# 11_Fun.net
KiCad netlist of a schematic drawn in Altium Designer
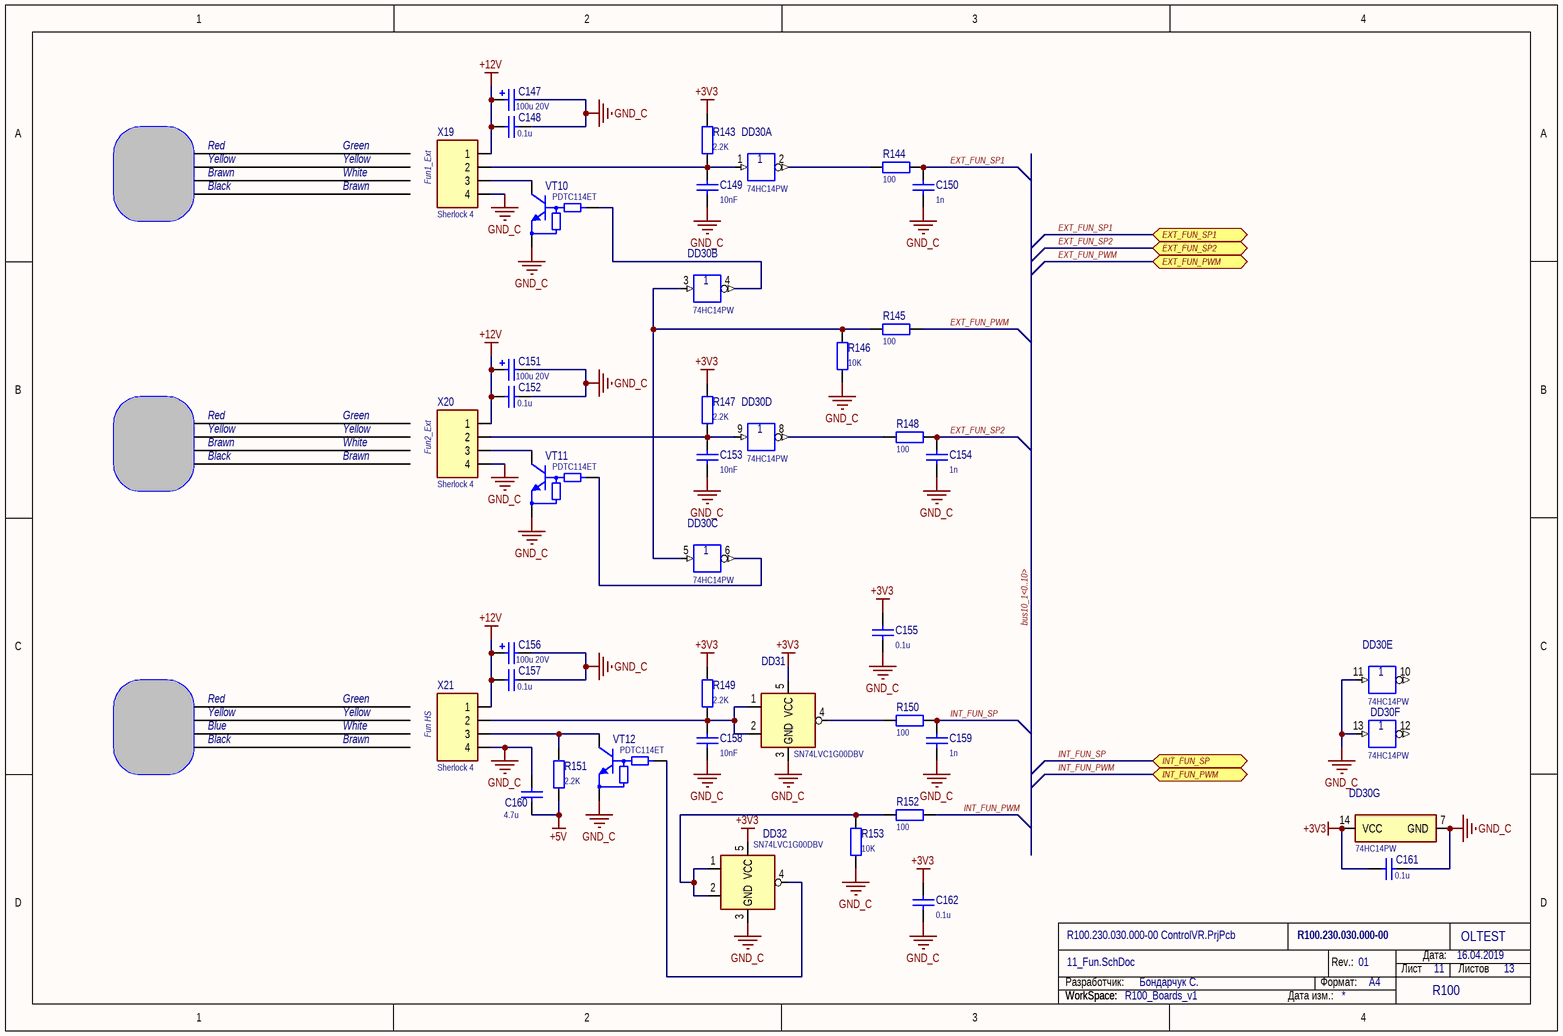
[diagram p0: 11_Fun.SchDoc]

(export (version "E")
  (design (tool "Eeschema 10.0.6"))
  (components
    (comp (ref "C147")
      (value "100u 20V")
      (footprint "mainLib:TAJD")
      (description "SMD SIZE D TANTALUM AVX 20V 10%")
      (fields (field (name "PARTNUMBER") "TAJD107K020RNJ") (field (name "MANUFACTURER") "AVX"))
      (libsource (lib "mainRCLib") (part "TECAP 100u 20V 10%"))
    )
    (comp (ref "C148")
      (value "0.1u")
      (footprint "mainLib:SMD_C_0603")
      (description "SMD C 0603 MURATA 50V 10% X7R")
      (fields (field (name "PARTNUMBER") "GRM188R71H104K") (field (name "MANUFACTURER") "MURATA"))
      (libsource (lib "mainRCLib") (part "C0603 0.1u 50V 10%"))
    )
    (comp (ref "C149")
      (value "10nF")
      (footprint "mainLib:SMD_C_0603")
      (description "SMD C 0603 MURATA 100V 10% X7R")
      (fields (field (name "PARTNUMBER") "GRJ188R72A103KE11#") (field (name "MANUFACTURER") "MURATA"))
      (libsource (lib "mainRCLib") (part "C0603 10nF 100V 10%"))
    )
    (comp (ref "C150")
      (value "1n")
      (footprint "mainLib:SMD_C_0603")
      (description "SMD C 0603 MURATA 50V 5% NP0")
      (fields (field (name "PARTNUMBER") "GRM1885C1H102JA01") (field (name "MANUFACTURER") "MURATA"))
      (libsource (lib "mainRCLib") (part "C0603 1n 50V 5%"))
    )
    (comp (ref "C151")
      (value "100u 20V")
      (footprint "mainLib:TAJD")
      (description "SMD SIZE D TANTALUM AVX 20V 10%")
      (fields (field (name "PARTNUMBER") "TAJD107K020RNJ") (field (name "MANUFACTURER") "AVX"))
      (libsource (lib "mainRCLib") (part "TECAP 100u 20V 10%"))
    )
    (comp (ref "C152")
      (value "0.1u")
      (footprint "mainLib:SMD_C_0603")
      (description "SMD C 0603 MURATA 50V 10% X7R")
      (fields (field (name "PARTNUMBER") "GRM188R71H104K") (field (name "MANUFACTURER") "MURATA"))
      (libsource (lib "mainRCLib") (part "C0603 0.1u 50V 10%"))
    )
    (comp (ref "C153")
      (value "10nF")
      (footprint "mainLib:SMD_C_0603")
      (description "SMD C 0603 MURATA 100V 10% X7R")
      (fields (field (name "PARTNUMBER") "GRJ188R72A103KE11#") (field (name "MANUFACTURER") "MURATA"))
      (libsource (lib "mainRCLib") (part "C0603 10nF 100V 10%"))
    )
    (comp (ref "C154")
      (value "1n")
      (footprint "mainLib:SMD_C_0603")
      (description "SMD C 0603 MURATA 50V 5% NP0")
      (fields (field (name "PARTNUMBER") "GRM1885C1H102JA01") (field (name "MANUFACTURER") "MURATA"))
      (libsource (lib "mainRCLib") (part "C0603 1n 50V 5%"))
    )
    (comp (ref "C155")
      (value "0.1u")
      (footprint "mainLib:SMD_C_0603")
      (description "SMD C 0603 MURATA 50V 10% X7R")
      (fields (field (name "PARTNUMBER") "GRM188R71H104K") (field (name "MANUFACTURER") "MURATA"))
      (libsource (lib "mainRCLib") (part "C0603 0.1u 50V 10%"))
    )
    (comp (ref "C156")
      (value "100u 20V")
      (footprint "mainLib:TAJD")
      (description "SMD SIZE D TANTALUM AVX 20V 10%")
      (fields (field (name "PARTNUMBER") "TAJD107K020RNJ") (field (name "MANUFACTURER") "AVX"))
      (libsource (lib "mainRCLib") (part "TECAP 100u 20V 10%"))
    )
    (comp (ref "C157")
      (value "0.1u")
      (footprint "mainLib:SMD_C_0603")
      (description "SMD C 0603 MURATA 50V 10% X7R")
      (fields (field (name "PARTNUMBER") "GRM188R71H104K") (field (name "MANUFACTURER") "MURATA"))
      (libsource (lib "mainRCLib") (part "C0603 0.1u 50V 10%"))
    )
    (comp (ref "C158")
      (value "10nF")
      (footprint "mainLib:SMD_C_0603")
      (description "SMD C 0603 MURATA 100V 10% X7R")
      (fields (field (name "PARTNUMBER") "GRJ188R72A103KE11#") (field (name "MANUFACTURER") "MURATA"))
      (libsource (lib "mainRCLib") (part "C0603 10nF 100V 10%"))
    )
    (comp (ref "C159")
      (value "1n")
      (footprint "mainLib:SMD_C_0603")
      (description "SMD C 0603 MURATA 50V 5% NP0")
      (fields (field (name "PARTNUMBER") "GRM1885C1H102JA01") (field (name "MANUFACTURER") "MURATA"))
      (libsource (lib "mainRCLib") (part "C0603 1n 50V 5%"))
    )
    (comp (ref "C160")
      (value "4.7u")
      (footprint "mainLib:SMD_C_0805")
      (description "SMD C 0805 MURATA 50V 5% NP0")
      (fields (field (name "PARTNUMBER") "GRM21BR61E475M") (field (name "MANUFACTURER") "MURATA"))
      (libsource (lib "mainRCLib") (part "C0805 4.7u 25V 20%  X5R"))
    )
    (comp (ref "C161")
      (value "0.1u")
      (footprint "mainLib:SMD_C_0603")
      (description "SMD C 0603 MURATA 50V 10% X7R")
      (fields (field (name "PARTNUMBER") "GRM188R71H104K") (field (name "MANUFACTURER") "MURATA"))
      (libsource (lib "mainRCLib") (part "C0603 0.1u 50V 10%"))
    )
    (comp (ref "C162")
      (value "0.1u")
      (footprint "mainLib:SMD_C_0603")
      (description "SMD C 0603 MURATA 50V 10% X7R")
      (fields (field (name "PARTNUMBER") "GRM188R71H104K") (field (name "MANUFACTURER") "MURATA"))
      (libsource (lib "mainRCLib") (part "C0603 0.1u 50V 10%"))
    )
    (comp (ref "DD30")
      (value "74HC14PW")
      (footprint "mainLib:TSSOP14")
      (description "Quadruple 2-Input Positive-OR Gates, PW0014A")
      (fields (field (name "MANUFACTURER") "Texas Instruments"))
      (libsource (lib "mainLib") (part "74HC14"))
    )
    (comp (ref "DD31")
      (value "SN74LVC1G00DBV")
      (footprint "mainLib:SOT-23(DBV)")
      (description "2-in NAND")
      (fields (field (name "MANUFACTURER") "Texas Instruments"))
      (libsource (lib "mainLib") (part "SN74LVC1G00DBV"))
    )
    (comp (ref "DD32")
      (value "SN74LVC1G00DBV")
      (footprint "mainLib:SOT-23(DBV)")
      (description "2-in NAND")
      (fields (field (name "MANUFACTURER") "Texas Instruments"))
      (libsource (lib "mainLib") (part "SN74LVC1G00DBV"))
    )
    (comp (ref "R143")
      (value "2.2K")
      (footprint "mainLib:SMD_R_0603")
      (description "SMD R 0603 VISHAY 0.1W 75V 1% 100ppm")
      (fields (field (name "PARTNUMBER") "CRCW06032K20FK") (field (name "MANUFACTURER") "VISHAY"))
      (libsource (lib "mainRCLib") (part "R0603 2.2K 1%"))
    )
    (comp (ref "R144")
      (value "100")
      (footprint "SMD_R_0603")
      (description "SMD R 0603 VISHAY 0.1W 75V 1% 100ppm")
      (fields (field (name "PARTNUMBER") "CRCW0603100RFK") (field (name "MANUFACTURER") "VISHAY"))
      (libsource (lib "mainRCLib") (part "R0603 100 1%"))
    )
    (comp (ref "R145")
      (value "100")
      (footprint "SMD_R_0603")
      (description "SMD R 0603 VISHAY 0.1W 75V 1% 100ppm")
      (fields (field (name "PARTNUMBER") "CRCW0603100RFK") (field (name "MANUFACTURER") "VISHAY"))
      (libsource (lib "mainRCLib") (part "R0603 100 1%"))
    )
    (comp (ref "R146")
      (value "10K")
      (footprint "SMD_R_0603")
      (description "SMD R 0603 VISHAY 0.1W 75V 1% 100ppm")
      (fields (field (name "PARTNUMBER") "CRCW060310K0FK") (field (name "MANUFACTURER") "VISHAY"))
      (libsource (lib "mainRCLib") (part "R0603 10К 1%"))
    )
    (comp (ref "R147")
      (value "2.2K")
      (footprint "mainLib:SMD_R_0603")
      (description "SMD R 0603 VISHAY 0.1W 75V 1% 100ppm")
      (fields (field (name "PARTNUMBER") "CRCW06032K20FK") (field (name "MANUFACTURER") "VISHAY"))
      (libsource (lib "mainRCLib") (part "R0603 2.2K 1%"))
    )
    (comp (ref "R148")
      (value "100")
      (footprint "SMD_R_0603")
      (description "SMD R 0603 VISHAY 0.1W 75V 1% 100ppm")
      (fields (field (name "PARTNUMBER") "CRCW0603100RFK") (field (name "MANUFACTURER") "VISHAY"))
      (libsource (lib "mainRCLib") (part "R0603 100 1%"))
    )
    (comp (ref "R149")
      (value "2.2K")
      (footprint "mainLib:SMD_R_0603")
      (description "SMD R 0603 VISHAY 0.1W 75V 1% 100ppm")
      (fields (field (name "PARTNUMBER") "CRCW06032K20FK") (field (name "MANUFACTURER") "VISHAY"))
      (libsource (lib "mainRCLib") (part "R0603 2.2K 1%"))
    )
    (comp (ref "R150")
      (value "100")
      (footprint "SMD_R_0603")
      (description "SMD R 0603 VISHAY 0.1W 75V 1% 100ppm")
      (fields (field (name "PARTNUMBER") "CRCW0603100RFK") (field (name "MANUFACTURER") "VISHAY"))
      (libsource (lib "mainRCLib") (part "R0603 100 1%"))
    )
    (comp (ref "R151")
      (value "2.2K")
      (footprint "mainLib:SMD_R_0603")
      (description "SMD R 0603 VISHAY 0.1W 75V 1% 100ppm")
      (fields (field (name "PARTNUMBER") "CRCW06032K20FK") (field (name "MANUFACTURER") "VISHAY"))
      (libsource (lib "mainRCLib") (part "R0603 2.2K 1%"))
    )
    (comp (ref "R152")
      (value "100")
      (footprint "SMD_R_0603")
      (description "SMD R 0603 VISHAY 0.1W 75V 1% 100ppm")
      (fields (field (name "PARTNUMBER") "CRCW0603100RFK") (field (name "MANUFACTURER") "VISHAY"))
      (libsource (lib "mainRCLib") (part "R0603 100 1%"))
    )
    (comp (ref "R153")
      (value "10K")
      (footprint "SMD_R_0603")
      (description "SMD R 0603 VISHAY 0.1W 75V 1% 100ppm")
      (fields (field (name "PARTNUMBER") "CRCW060310K0FK") (field (name "MANUFACTURER") "VISHAY"))
      (libsource (lib "mainRCLib") (part "R0603 10К 1%"))
    )
    (comp (ref "VT10")
      (value "PDTC114ET")
      (footprint "mainLib:SOT23-3")
      (description "Digital Transistor (BRT), R1=10 kOhm, R2=10 kOhm, NPN Transistor")
      (fields (field (name "MANUFACTURER") "On Semiconductor"))
      (libsource (lib "mainLib") (part "PDTC114ET"))
    )
    (comp (ref "VT11")
      (value "PDTC114ET")
      (footprint "mainLib:SOT23-3")
      (description "Digital Transistor (BRT), R1=10 kOhm, R2=10 kOhm, NPN Transistor")
      (fields (field (name "MANUFACTURER") "On Semiconductor"))
      (libsource (lib "mainLib") (part "PDTC114ET"))
    )
    (comp (ref "VT12")
      (value "PDTC114ET")
      (footprint "mainLib:SOT23-3")
      (description "Digital Transistor (BRT), R1=10 kOhm, R2=10 kOhm, NPN Transistor")
      (fields (field (name "MANUFACTURER") "On Semiconductor"))
      (libsource (lib "mainLib") (part "PDTC114ET"))
    )
    (comp (ref "X19")
      (value "Sherlock 4")
      (footprint "35362-0450")
      (description "Sherlock 4 Top, 2A 125V 2mm")
      (fields (field (name "PARTNUMBER") "35362-0450") (field (name "MANUFACTURER") "MOLEX"))
      (libsource (lib "mainLib") (part "35362-0450"))
    )
    (comp (ref "X20")
      (value "Sherlock 4")
      (footprint "35362-0450")
      (description "Sherlock 4 Top, 2A 125V 2mm")
      (fields (field (name "PARTNUMBER") "35362-0450") (field (name "MANUFACTURER") "MOLEX"))
      (libsource (lib "mainLib") (part "35362-0450"))
    )
    (comp (ref "X21")
      (value "Sherlock 4")
      (footprint "35362-0450")
      (description "Sherlock 4 Top, 2A 125V 2mm")
      (fields (field (name "PARTNUMBER") "35362-0450") (field (name "MANUFACTURER") "MOLEX"))
      (libsource (lib "mainLib") (part "35362-0450"))
    )
  )
  (nets
    (net (code "2") (name "+3V3") (class "Default")
      (node (ref "C155") (pin "2") (pinfunction "2_2") (pintype "passive"))
      (node (ref "C161") (pin "1") (pinfunction "1_1") (pintype "passive"))
      (node (ref "C162") (pin "2") (pinfunction "2_2") (pintype "passive"))
      (node (ref "DD30") (pin "14") (pinfunction "VCC_14") (pintype "power_in"))
      (node (ref "DD31") (pin "5") (pinfunction "VCC_5") (pintype "passive"))
      (node (ref "DD32") (pin "5") (pinfunction "VCC_5") (pintype "passive"))
      (node (ref "R143") (pin "2") (pinfunction "2_2") (pintype "passive"))
      (node (ref "R147") (pin "2") (pinfunction "2_2") (pintype "passive"))
      (node (ref "R149") (pin "2") (pinfunction "2_2") (pintype "passive"))
    )
    (net (code "3") (name "+5V") (class "Default")
      (node (ref "C160") (pin "1") (pinfunction "1_1") (pintype "passive"))
      (node (ref "R151") (pin "1") (pinfunction "1_1") (pintype "passive"))
    )
    (net (code "4") (name "+12V") (class "Default")
      (node (ref "C147") (pin "1") (pinfunction "1_1") (pintype "passive"))
      (node (ref "C148") (pin "1") (pinfunction "1_1") (pintype "passive"))
      (node (ref "C151") (pin "1") (pinfunction "1_1") (pintype "passive"))
      (node (ref "C152") (pin "1") (pinfunction "1_1") (pintype "passive"))
      (node (ref "C156") (pin "1") (pinfunction "1_1") (pintype "passive"))
      (node (ref "C157") (pin "1") (pinfunction "1_1") (pintype "passive"))
      (node (ref "X19") (pin "1") (pinfunction "1_1") (pintype "passive"))
      (node (ref "X20") (pin "1") (pinfunction "1_1") (pintype "passive"))
      (node (ref "X21") (pin "1") (pinfunction "1_1") (pintype "passive"))
    )
    (net (code "5") (name "/EXT_FUN_PWM") (class "Default")
      (node (ref "R145") (pin "2") (pinfunction "2_2") (pintype "passive"))
    )
    (net (code "6") (name "/EXT_FUN_SP1") (class "Default")
      (node (ref "C150") (pin "2") (pinfunction "2_2") (pintype "passive"))
      (node (ref "R144") (pin "2") (pinfunction "2_2") (pintype "passive"))
    )
    (net (code "7") (name "/EXT_FUN_SP2") (class "Default")
      (node (ref "C154") (pin "2") (pinfunction "2_2") (pintype "passive"))
      (node (ref "R148") (pin "2") (pinfunction "2_2") (pintype "passive"))
    )
    (net (code "8") (name "/INT_FUN_PWM") (class "Default")
      (node (ref "R152") (pin "2") (pinfunction "2_2") (pintype "passive"))
    )
    (net (code "9") (name "/INT_FUN_SP") (class "Default")
      (node (ref "C159") (pin "2") (pinfunction "2_2") (pintype "passive"))
      (node (ref "R150") (pin "2") (pinfunction "2_2") (pintype "passive"))
    )
    (net (code "11") (name "GND_C") (class "Default")
      (node (ref "C147") (pin "2") (pinfunction "2_2") (pintype "passive"))
      (node (ref "C148") (pin "2") (pinfunction "2_2") (pintype "passive"))
      (node (ref "C149") (pin "2") (pinfunction "2_2") (pintype "passive"))
      (node (ref "C150") (pin "1") (pinfunction "1_1") (pintype "passive"))
      (node (ref "C151") (pin "2") (pinfunction "2_2") (pintype "passive"))
      (node (ref "C152") (pin "2") (pinfunction "2_2") (pintype "passive"))
      (node (ref "C153") (pin "2") (pinfunction "2_2") (pintype "passive"))
      (node (ref "C154") (pin "1") (pinfunction "1_1") (pintype "passive"))
      (node (ref "C155") (pin "1") (pinfunction "1_1") (pintype "passive"))
      (node (ref "C156") (pin "2") (pinfunction "2_2") (pintype "passive"))
      (node (ref "C157") (pin "2") (pinfunction "2_2") (pintype "passive"))
      (node (ref "C158") (pin "2") (pinfunction "2_2") (pintype "passive"))
      (node (ref "C159") (pin "1") (pinfunction "1_1") (pintype "passive"))
      (node (ref "C160") (pin "2") (pinfunction "2_2") (pintype "passive"))
      (node (ref "C161") (pin "2") (pinfunction "2_2") (pintype "passive"))
      (node (ref "C162") (pin "1") (pinfunction "1_1") (pintype "passive"))
      (node (ref "DD30") (pin "11") (pinfunction "5A_11") (pintype "input"))
      (node (ref "DD30") (pin "13") (pinfunction "6A_13") (pintype "input"))
      (node (ref "DD30") (pin "7") (pinfunction "GND_7") (pintype "power_in"))
      (node (ref "DD31") (pin "3") (pinfunction "GND_3") (pintype "passive"))
      (node (ref "DD32") (pin "3") (pinfunction "GND_3") (pintype "passive"))
      (node (ref "R146") (pin "1") (pinfunction "1_1") (pintype "passive"))
      (node (ref "R153") (pin "1") (pinfunction "1_1") (pintype "passive"))
      (node (ref "VT10") (pin "2") (pinfunction "E_2") (pintype "passive"))
      (node (ref "VT11") (pin "2") (pinfunction "E_2") (pintype "passive"))
      (node (ref "VT12") (pin "2") (pinfunction "E_2") (pintype "passive"))
      (node (ref "X19") (pin "4") (pinfunction "4_4") (pintype "passive"))
      (node (ref "X20") (pin "4") (pinfunction "4_4") (pintype "passive"))
      (node (ref "X21") (pin "4") (pinfunction "4_4") (pintype "passive"))
    )
    (net (code "12") (name "Net-(C158-Pad1)") (class "Default")
      (node (ref "C158") (pin "1") (pinfunction "1_1") (pintype "passive"))
      (node (ref "DD31") (pin "1") (pintype "passive"))
      (node (ref "DD31") (pin "2") (pintype "passive"))
      (node (ref "R149") (pin "1") (pinfunction "1_1") (pintype "passive"))
      (node (ref "X21") (pin "2") (pinfunction "2_2") (pintype "passive"))
    )
    (net (code "13") (name "Net-(DD30A-1A)") (class "Default")
      (node (ref "C149") (pin "1") (pinfunction "1_1") (pintype "passive"))
      (node (ref "DD30") (pin "1") (pinfunction "1A_1") (pintype "input"))
      (node (ref "R143") (pin "1") (pinfunction "1_1") (pintype "passive"))
      (node (ref "X19") (pin "2") (pinfunction "2_2") (pintype "passive"))
    )
    (net (code "14") (name "Net-(DD30A-1Y)") (class "Default")
      (node (ref "DD30") (pin "2") (pinfunction "1Y_2") (pintype "output"))
      (node (ref "R144") (pin "1") (pinfunction "1_1") (pintype "passive"))
    )
    (net (code "15") (name "Net-(DD30B-2A)") (class "Default")
      (node (ref "DD30") (pin "3") (pinfunction "2A_3") (pintype "input"))
      (node (ref "DD30") (pin "5") (pinfunction "3A_5") (pintype "input"))
      (node (ref "R145") (pin "1") (pinfunction "1_1") (pintype "passive"))
      (node (ref "R146") (pin "2") (pinfunction "2_2") (pintype "passive"))
    )
    (net (code "16") (name "Net-(DD30B-2Y)") (class "Default")
      (node (ref "DD30") (pin "4") (pinfunction "2Y_4") (pintype "output"))
      (node (ref "VT10") (pin "1") (pinfunction "B_1") (pintype "passive"))
    )
    (net (code "17") (name "Net-(DD30C-3Y)") (class "Default")
      (node (ref "DD30") (pin "6") (pinfunction "3Y_6") (pintype "output"))
      (node (ref "VT11") (pin "1") (pinfunction "B_1") (pintype "passive"))
    )
    (net (code "18") (name "Net-(DD30D-4A)") (class "Default")
      (node (ref "C153") (pin "1") (pinfunction "1_1") (pintype "passive"))
      (node (ref "DD30") (pin "9") (pinfunction "4A_9") (pintype "input"))
      (node (ref "R147") (pin "1") (pinfunction "1_1") (pintype "passive"))
      (node (ref "X20") (pin "2") (pinfunction "2_2") (pintype "passive"))
    )
    (net (code "19") (name "Net-(DD30D-4Y)") (class "Default")
      (node (ref "DD30") (pin "8") (pinfunction "4Y_8") (pintype "output"))
      (node (ref "R148") (pin "1") (pinfunction "1_1") (pintype "passive"))
    )
    (net (code "20") (name "Net-(DD31-Pad4)") (class "Default")
      (node (ref "DD31") (pin "4") (pintype "passive"))
      (node (ref "R150") (pin "1") (pinfunction "1_1") (pintype "passive"))
    )
    (net (code "21") (name "Net-(DD32-Pad1)") (class "Default")
      (node (ref "DD32") (pin "1") (pintype "passive"))
      (node (ref "DD32") (pin "2") (pintype "passive"))
      (node (ref "R152") (pin "1") (pinfunction "1_1") (pintype "passive"))
      (node (ref "R153") (pin "2") (pinfunction "2_2") (pintype "passive"))
    )
    (net (code "22") (name "Net-(VT10-C)") (class "Default")
      (node (ref "VT10") (pin "3") (pinfunction "C_3") (pintype "passive"))
      (node (ref "X19") (pin "3") (pinfunction "3_3") (pintype "passive"))
    )
    (net (code "23") (name "Net-(VT11-C)") (class "Default")
      (node (ref "VT11") (pin "3") (pinfunction "C_3") (pintype "passive"))
      (node (ref "X20") (pin "3") (pinfunction "3_3") (pintype "passive"))
    )
    (net (code "24") (name "Net-(VT12-B)") (class "Default")
      (node (ref "DD32") (pin "4") (pintype "passive"))
      (node (ref "VT12") (pin "1") (pinfunction "B_1") (pintype "passive"))
    )
    (net (code "25") (name "Net-(VT12-C)") (class "Default")
      (node (ref "R151") (pin "2") (pinfunction "2_2") (pintype "passive"))
      (node (ref "VT12") (pin "3") (pinfunction "C_3") (pintype "passive"))
      (node (ref "X21") (pin "3") (pinfunction "3_3") (pintype "passive"))
    )
    (net (code "26") (name "unconnected-(DD30E-5Y-Pad10)") (class "Default")
      (node (ref "DD30") (pin "10") (pinfunction "5Y_10") (pintype "output"))
    )
    (net (code "27") (name "unconnected-(DD30F-6Y-Pad12)") (class "Default")
      (node (ref "DD30") (pin "12") (pinfunction "6Y_12") (pintype "output"))
    )
  )
)
